# DE-080324.net
KiCad netlist of a schematic drawn in Altium Designer
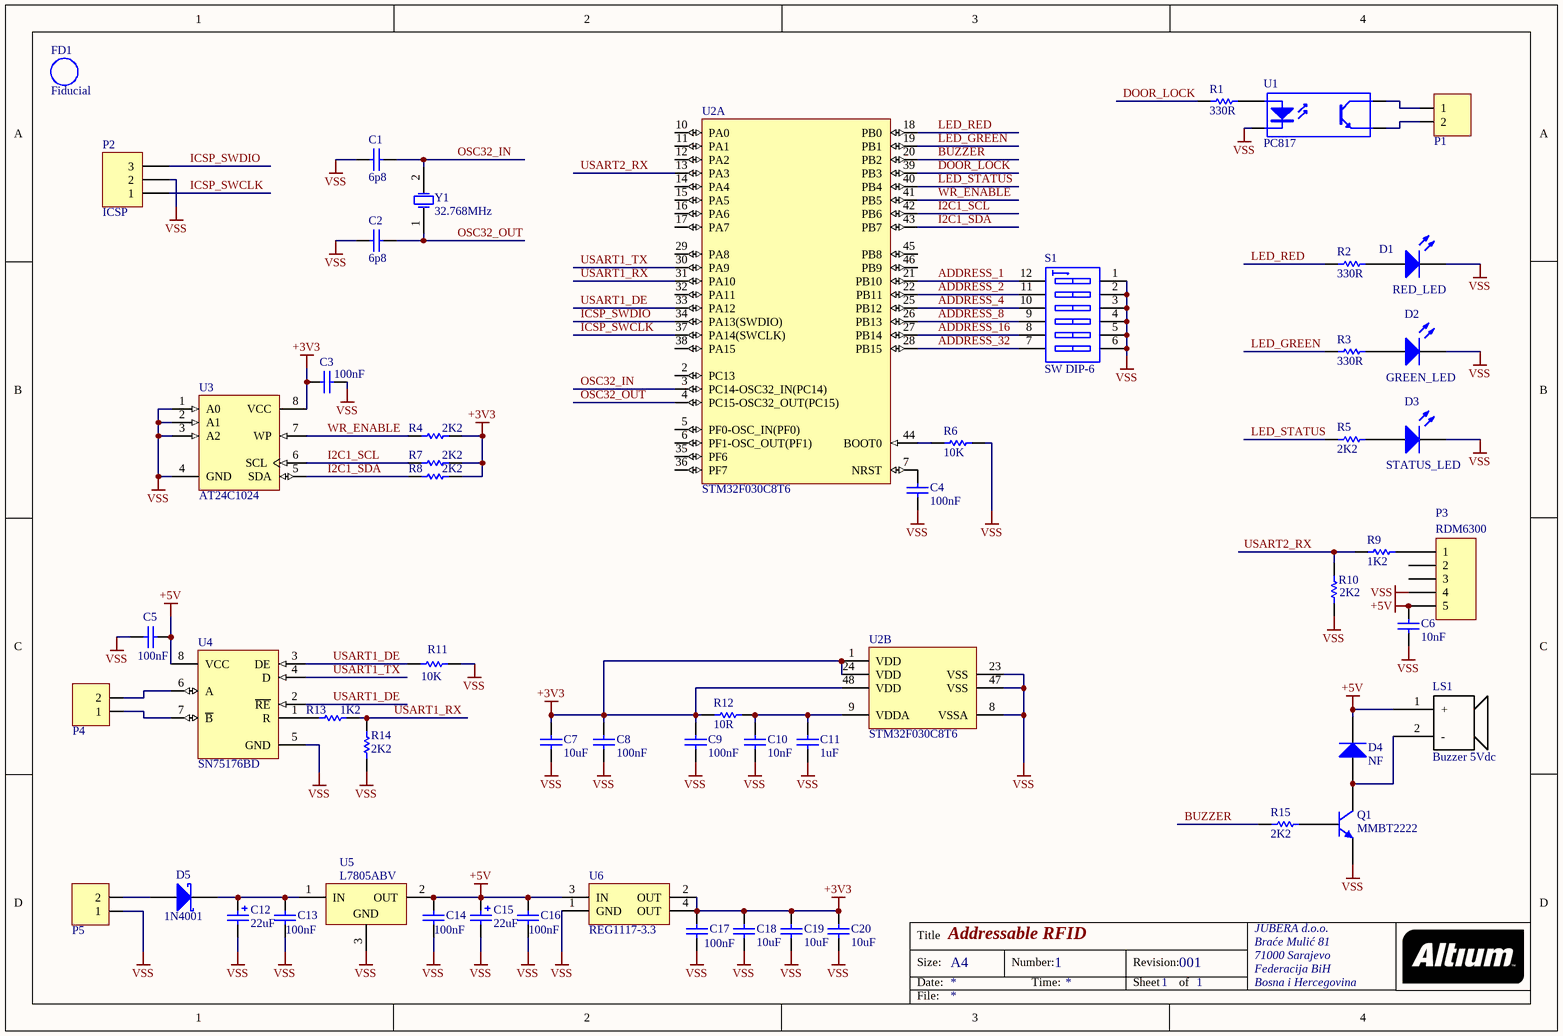
[diagram p0: DE-080324.SchDoc]

(export (version "E")
  (design (tool "Eeschema 10.0.6"))
  (components
    (comp (ref "C1")
      (value "6p8")
      (footprint "0603")
      (description "Ceramic Chip Capacitor - Standard")
      (fields (field (name "PUBLISHER") "Altium Limited"))
      (libsource (lib "DE-080324") (part "C0603"))
    )
    (comp (ref "C2")
      (value "6p8")
      (footprint "0603")
      (description "Ceramic Chip Capacitor - Standard")
      (fields (field (name "PUBLISHER") "Altium Limited"))
      (libsource (lib "DE-080324") (part "C0603"))
    )
    (comp (ref "C3")
      (value "100nF")
      (footprint "0603")
      (description "Ceramic Chip Capacitor - Standard")
      (fields (field (name "PUBLISHER") "Altium Limited"))
      (libsource (lib "DE-080324") (part "C0603"))
    )
    (comp (ref "C4")
      (value "100nF")
      (footprint "0603")
      (description "Ceramic Chip Capacitor - Standard")
      (fields (field (name "PUBLISHER") "Altium Limited"))
      (libsource (lib "DE-080324") (part "C0603"))
    )
    (comp (ref "C5")
      (value "100nF")
      (footprint "0603")
      (description "Ceramic Chip Capacitor - Standard")
      (fields (field (name "PUBLISHER") "Altium Limited"))
      (libsource (lib "DE-080324") (part "C0603"))
    )
    (comp (ref "C6")
      (value "10nF")
      (footprint "0603")
      (description "Ceramic Chip Capacitor - Standard")
      (fields (field (name "PUBLISHER") "Altium Limited"))
      (libsource (lib "DE-080324") (part "C0603"))
    )
    (comp (ref "C7")
      (value "10uF")
      (footprint "0805")
      (description "Ceramic Chip Capacitor - Standard")
      (fields (field (name "PUBLISHER") "Altium Limited"))
      (libsource (lib "DE-080324") (part "C0805"))
    )
    (comp (ref "C8")
      (value "100nF")
      (footprint "0603")
      (description "Ceramic Chip Capacitor - Standard")
      (fields (field (name "PUBLISHER") "Altium Limited"))
      (libsource (lib "DE-080324") (part "C0603"))
    )
    (comp (ref "C9")
      (value "100nF")
      (footprint "0603")
      (description "Ceramic Chip Capacitor - Standard")
      (fields (field (name "PUBLISHER") "Altium Limited"))
      (libsource (lib "DE-080324") (part "C0603"))
    )
    (comp (ref "C10")
      (value "10nF")
      (footprint "0603")
      (description "Ceramic Chip Capacitor - Standard")
      (fields (field (name "PUBLISHER") "Altium Limited"))
      (libsource (lib "DE-080324") (part "C0603"))
    )
    (comp (ref "C11")
      (value "1uF")
      (footprint "0603")
      (description "Ceramic Chip Capacitor - Standard")
      (fields (field (name "PUBLISHER") "Altium Limited"))
      (libsource (lib "DE-080324") (part "C0603"))
    )
    (comp (ref "C12")
      (value "22uF")
      (footprint "CAPPR2-5X11")
      (description "Aluminum Electrolytic Capacitor, Radial Style with Long Leads: 47uF, 35V")
      (fields (field (name "PUBLISHER") "Altium Limited"))
      (libsource (lib "DE-080324") (part "EKA00AA247F00"))
    )
    (comp (ref "C13")
      (value "100nF")
      (footprint "0603")
      (description "Ceramic Chip Capacitor - Standard")
      (fields (field (name "PUBLISHER") "Altium Limited"))
      (libsource (lib "DE-080324") (part "C0603"))
    )
    (comp (ref "C14")
      (value "100nF")
      (footprint "0603")
      (description "Ceramic Chip Capacitor - Standard")
      (fields (field (name "PUBLISHER") "Altium Limited"))
      (libsource (lib "DE-080324") (part "C0603"))
    )
    (comp (ref "C15")
      (value "22uF")
      (footprint "CAPPR2-5X11")
      (description "Aluminum Electrolytic Capacitor, Radial Style with Long Leads: 47uF, 35V")
      (fields (field (name "PUBLISHER") "Altium Limited"))
      (libsource (lib "DE-080324") (part "EKA00AA247F00"))
    )
    (comp (ref "C16")
      (value "100nF")
      (footprint "0603")
      (description "Ceramic Chip Capacitor - Standard")
      (fields (field (name "PUBLISHER") "Altium Limited"))
      (libsource (lib "DE-080324") (part "C0603"))
    )
    (comp (ref "C17")
      (value "100nF")
      (footprint "0603")
      (description "Ceramic Chip Capacitor - Standard")
      (fields (field (name "PUBLISHER") "Altium Limited"))
      (libsource (lib "DE-080324") (part "C0603"))
    )
    (comp (ref "C18")
      (value "10uF")
      (footprint "0805")
      (description "Ceramic Chip Capacitor - Standard")
      (fields (field (name "PUBLISHER") "Altium Limited"))
      (libsource (lib "DE-080324") (part "C0805"))
    )
    (comp (ref "C19")
      (value "10uF")
      (footprint "0805")
      (description "Ceramic Chip Capacitor - Standard")
      (fields (field (name "PUBLISHER") "Altium Limited"))
      (libsource (lib "DE-080324") (part "C0805"))
    )
    (comp (ref "C20")
      (value "10uF")
      (footprint "0805")
      (description "Ceramic Chip Capacitor - Standard")
      (fields (field (name "PUBLISHER") "Altium Limited"))
      (libsource (lib "DE-080324") (part "C0805"))
    )
    (comp (ref "D1")
      (value "RED_LED")
      (footprint "2.0X1.25X1.2")
      (description "Top Mount AS AlInGaP Red Oval Lens High Brightness")
      (fields (field (name "PUBLISHER") "Altium Limited"))
      (libsource (lib "DE-080324") (part "HSMC-C540-F0001"))
    )
    (comp (ref "D2")
      (value "GREEN_LED")
      (footprint "2.0X1.25X1.2")
      (description "Top Mount AS AlInGaP Red Oval Lens High Brightness")
      (fields (field (name "PUBLISHER") "Altium Limited"))
      (libsource (lib "DE-080324") (part "HSMC-C540-F0001"))
    )
    (comp (ref "D3")
      (value "STATUS_LED")
      (footprint "2.0X1.25X1.2")
      (description "Top Mount AS AlInGaP Red Oval Lens High Brightness")
      (fields (field (name "PUBLISHER") "Altium Limited"))
      (libsource (lib "DE-080324") (part "HSMC-C540-F0001"))
    )
    (comp (ref "D4")
      (value "NF")
      (footprint "SOD323")
      (description "General-purpose Diode")
      (fields (field (name "PUBLISHER") "Altium Limited"))
      (libsource (lib "DE-080324") (part "BAS321"))
    )
    (comp (ref "D5")
      (value "1N4001")
      (footprint "SMB")
      (description "Schottky Rectifier")
      (fields (field (name "PUBLISHER") "Altium Limited"))
      (libsource (lib "DE-080324") (part "10BQ100"))
    )
    (comp (ref "FD1")
      (value "Fiducial")
      (footprint "Fiducial")
      (description "Fiduchial mark")
      (libsource (lib "DE-080324") (part "Fiduchial"))
    )
    (comp (ref "LS1")
      (value "Buzzer 5Vdc")
      (footprint "BUZZER")
      (description "5Vdc PCB buzzer")
      (libsource (lib "DE-080324") (part "BUZZER"))
    )
    (comp (ref "P1")
      (value "TERMINAL BLOK 2")
      (footprint "TERMINAL BLOK 2")
      (description "2 pinski terminal blok")
      (libsource (lib "") (part "TERMINAL BLOK 2_1"))
    )
    (comp (ref "P2")
      (value "ICSP")
      (footprint "HDR1X3")
      (description "Header, 3-Pin")
      (fields (field (name "PUBLISHER") "Altium Limited"))
      (libsource (lib "Miscellaneous Connectors") (part "Header 3"))
    )
    (comp (ref "P3")
      (value "RDM6300")
      (footprint "HDR1X5")
      (description "Header, 5-Pin")
      (fields (field (name "PUBLISHER") "Altium Limited"))
      (libsource (lib "Miscellaneous Connectors") (part "Header 5"))
    )
    (comp (ref "P4")
      (value "TERMINAL BLOK 2")
      (footprint "TERMINAL BLOK 2")
      (description "2 pinski terminal blok")
      (libsource (lib "DE-080324") (part "TERMINAL BLOK 2"))
    )
    (comp (ref "P5")
      (value "TERMINAL BLOK 2")
      (footprint "TERMINAL BLOK 2")
      (description "2 pinski terminal blok")
      (libsource (lib "DE-080324") (part "TERMINAL BLOK 2"))
    )
    (comp (ref "Q1")
      (value "MMBT2222")
      (footprint "SOT23_N")
      (description "NPN General-purpose Transistor")
      (fields (field (name "PUBLISHER") "Altium Limited"))
      (libsource (lib "DE-080324") (part "BC817"))
    )
    (comp (ref "R1")
      (value "330R")
      (footprint "ERA-0603")
      (fields (field (name "PUBLISHER") "Altium Limited"))
      (libsource (lib "DE-080324") (part "ERAV"))
    )
    (comp (ref "R2")
      (value "330R")
      (footprint "ERA-0603")
      (fields (field (name "PUBLISHER") "Altium Limited"))
      (libsource (lib "DE-080324") (part "ERAV"))
    )
    (comp (ref "R3")
      (value "330R")
      (footprint "ERA-0603")
      (fields (field (name "PUBLISHER") "Altium Limited"))
      (libsource (lib "DE-080324") (part "ERAV"))
    )
    (comp (ref "R4")
      (value "2K2")
      (footprint "ERA-0603")
      (fields (field (name "PUBLISHER") "Altium Limited"))
      (libsource (lib "DE-080324") (part "ERAV"))
    )
    (comp (ref "R5")
      (value "2K2")
      (footprint "ERA-0603")
      (fields (field (name "PUBLISHER") "Altium Limited"))
      (libsource (lib "DE-080324") (part "ERAV"))
    )
    (comp (ref "R6")
      (value "10K")
      (footprint "ERA-0603")
      (fields (field (name "PUBLISHER") "Altium Limited"))
      (libsource (lib "DE-080324") (part "ERAV"))
    )
    (comp (ref "R7")
      (value "2K2")
      (footprint "ERA-0603")
      (fields (field (name "PUBLISHER") "Altium Limited"))
      (libsource (lib "DE-080324") (part "ERAV"))
    )
    (comp (ref "R8")
      (value "2K2")
      (footprint "ERA-0603")
      (fields (field (name "PUBLISHER") "Altium Limited"))
      (libsource (lib "DE-080324") (part "ERAV"))
    )
    (comp (ref "R9")
      (value "1K2")
      (footprint "ERA-0603")
      (fields (field (name "PUBLISHER") "Altium Limited"))
      (libsource (lib "DE-080324") (part "ERAV"))
    )
    (comp (ref "R10")
      (value "2K2")
      (footprint "ERA-0603")
      (fields (field (name "PUBLISHER") "Altium Limited"))
      (libsource (lib "DE-080324") (part "ERAV"))
    )
    (comp (ref "R11")
      (value "10K")
      (footprint "ERA-0603")
      (fields (field (name "PUBLISHER") "Altium Limited"))
      (libsource (lib "DE-080324") (part "ERAV"))
    )
    (comp (ref "R12")
      (value "10R")
      (footprint "ERA-0603")
      (fields (field (name "PUBLISHER") "Altium Limited"))
      (libsource (lib "DE-080324") (part "ERAV"))
    )
    (comp (ref "R13")
      (value "1K2")
      (footprint "ERA-0603")
      (fields (field (name "PUBLISHER") "Altium Limited"))
      (libsource (lib "DE-080324") (part "ERAV"))
    )
    (comp (ref "R14")
      (value "2K2")
      (footprint "ERA-0603")
      (fields (field (name "PUBLISHER") "Altium Limited"))
      (libsource (lib "DE-080324") (part "ERAV"))
    )
    (comp (ref "R15")
      (value "2K2")
      (footprint "ERA-0603")
      (fields (field (name "PUBLISHER") "Altium Limited"))
      (libsource (lib "DE-080324") (part "ERAV"))
    )
    (comp (ref "S1")
      (value "SW DIP-6")
      (footprint "DIP-12/SW")
      (description "DIP Switch, 6 Position, SPST")
      (fields (field (name "PUBLISHER") "Altium Limited"))
      (libsource (lib "Miscellaneous Devices") (part "SW DIP-6"))
    )
    (comp (ref "U1")
      (value "PC817")
      (footprint "SOP4")
      (description "4-Pin Phototransistor Optocoupler")
      (fields (field (name "PUBLISHER") "Altium Limited"))
      (libsource (lib "DE-080324") (part "PC817 optocoupler"))
    )
    (comp (ref "U2")
      (value "STM32F030C8T6")
      (footprint "STM-LQFP48_N")
      (libsource (lib "STMicroelectronics STM32 F0") (part "STM32F030C8T6"))
    )
    (comp (ref "U3")
      (value "AT24C1024")
      (footprint "8A2_L")
      (fields (field (name "PUBLISHER") "Altium Limited"))
      (libsource (lib "Atmel Memory Serial EEPROM") (part "AT24C02B-TP25-T"))
    )
    (comp (ref "U4")
      (value "SN75176BD")
      (footprint "D008_L")
      (description "Differential Bus Transceiver")
      (fields (field (name "PUBLISHER") "Altium Limited"))
      (libsource (lib "DE-080324") (part "SN75176BD"))
    )
    (comp (ref "U5")
      (value "L7805ABV")
      (footprint "TO220ABN")
      (description "Precision 1A Regulator")
      (fields (field (name "PUBLISHER") "Altium Limited"))
      (libsource (lib "ST Power Mgt Voltage Regulator") (part "L7805ABV"))
    )
    (comp (ref "U6")
      (value "REG1117-3.3")
      (footprint "ZZ311")
      (description "800mA and 1A Low Dropout Positive Regulator 2.85V, 3.3V, 5V, and Adjustable")
      (fields (field (name "PUBLISHER") "Altium Limited"))
      (libsource (lib "DE-080324") (part "REG1117-3.3"))
    )
    (comp (ref "Y1")
      (value "32.768MHz")
      (footprint "R26")
      (description "Tuning Fork Crystal Unit")
      (fields (field (name "PUBLISHER") "Altium Limited"))
      (libsource (lib "DE-080324") (part "R26-32.768"))
    )
  )
  (nets
    (net (code "1") (name "+3V3") (class "Default")
      (node (ref "C17") (pin "2") (pinfunction "2_2") (pintype "passive"))
      (node (ref "C18") (pin "2") (pinfunction "2_2") (pintype "passive"))
      (node (ref "C19") (pin "2") (pinfunction "2_2") (pintype "passive"))
      (node (ref "C20") (pin "2") (pinfunction "2_2") (pintype "passive"))
      (node (ref "C3") (pin "1") (pinfunction "1_1") (pintype "passive"))
      (node (ref "C7") (pin "2") (pinfunction "2_2") (pintype "passive"))
      (node (ref "C8") (pin "2") (pinfunction "2_2") (pintype "passive"))
      (node (ref "C9") (pin "2") (pinfunction "2_2") (pintype "passive"))
      (node (ref "R12") (pin "1") (pinfunction "1_1") (pintype "passive"))
      (node (ref "R4") (pin "2") (pinfunction "2_2") (pintype "passive"))
      (node (ref "R7") (pin "2") (pinfunction "2_2") (pintype "passive"))
      (node (ref "R8") (pin "2") (pinfunction "2_2") (pintype "passive"))
      (node (ref "U2") (pin "1") (pinfunction "VDD_1") (pintype "power_in"))
      (node (ref "U2") (pin "24") (pinfunction "VDD_24") (pintype "power_in"))
      (node (ref "U2") (pin "48") (pinfunction "VDD_48") (pintype "power_in"))
      (node (ref "U3") (pin "8") (pinfunction "VCC_8") (pintype "power_in"))
      (node (ref "U6") (pin "2") (pinfunction "OUT_2") (pintype "power_in"))
      (node (ref "U6") (pin "4") (pinfunction "OUT_4") (pintype "power_in"))
    )
    (net (code "2") (name "+5V") (class "Default")
      (node (ref "C14") (pin "2") (pinfunction "2_2") (pintype "passive"))
      (node (ref "C15") (pin "1") (pinfunction "1_1") (pintype "passive"))
      (node (ref "C16") (pin "2") (pinfunction "2_2") (pintype "passive"))
      (node (ref "C5") (pin "2") (pinfunction "2_2") (pintype "passive"))
      (node (ref "C6") (pin "2") (pinfunction "2_2") (pintype "passive"))
      (node (ref "D4") (pin "1") (pinfunction "K_1") (pintype "passive"))
      (node (ref "LS1") (pin "1") (pinfunction "+_1") (pintype "passive"))
      (node (ref "P3") (pin "5") (pinfunction "5_5") (pintype "passive"))
      (node (ref "U4") (pin "8") (pinfunction "VCC_8") (pintype "power_in"))
      (node (ref "U5") (pin "2") (pinfunction "OUT_2") (pintype "power_in"))
      (node (ref "U6") (pin "3") (pinfunction "IN_3") (pintype "power_in"))
    )
    (net (code "3") (name "/ADDRESS_1") (class "Default")
      (node (ref "S1") (pin "12") (pinfunction "B1_12") (pintype "passive"))
      (node (ref "U2") (pin "21") (pinfunction "PB10_21") (pintype "bidirectional"))
    )
    (net (code "4") (name "/ADDRESS_2") (class "Default")
      (node (ref "S1") (pin "11") (pinfunction "B2_11") (pintype "passive"))
      (node (ref "U2") (pin "22") (pinfunction "PB11_22") (pintype "bidirectional"))
    )
    (net (code "5") (name "/ADDRESS_4") (class "Default")
      (node (ref "S1") (pin "10") (pinfunction "B3_10") (pintype "passive"))
      (node (ref "U2") (pin "25") (pinfunction "PB12_25") (pintype "bidirectional"))
    )
    (net (code "6") (name "/ADDRESS_8") (class "Default")
      (node (ref "S1") (pin "9") (pinfunction "B4_9") (pintype "passive"))
      (node (ref "U2") (pin "26") (pinfunction "PB13_26") (pintype "bidirectional"))
    )
    (net (code "7") (name "/ADDRESS_16") (class "Default")
      (node (ref "S1") (pin "8") (pinfunction "B5_8") (pintype "passive"))
      (node (ref "U2") (pin "27") (pinfunction "PB14_27") (pintype "bidirectional"))
    )
    (net (code "8") (name "/ADDRESS_32") (class "Default")
      (node (ref "S1") (pin "7") (pinfunction "B6_7") (pintype "passive"))
      (node (ref "U2") (pin "28") (pinfunction "PB15_28") (pintype "bidirectional"))
    )
    (net (code "9") (name "/BUZZER") (class "Default")
      (node (ref "R15") (pin "1") (pinfunction "1_1") (pintype "passive"))
      (node (ref "U2") (pin "20") (pinfunction "PB2_20") (pintype "bidirectional"))
    )
    (net (code "10") (name "/DOOR_LOCK") (class "Default")
      (node (ref "R1") (pin "1") (pinfunction "1_1") (pintype "passive"))
      (node (ref "U2") (pin "39") (pinfunction "PB3_39") (pintype "bidirectional"))
    )
    (net (code "11") (name "/I2C1_SCL") (class "Default")
      (node (ref "R7") (pin "1") (pinfunction "1_1") (pintype "passive"))
      (node (ref "U2") (pin "42") (pinfunction "PB6_42") (pintype "bidirectional"))
      (node (ref "U3") (pin "6") (pinfunction "SCL_6") (pintype "input"))
    )
    (net (code "12") (name "/I2C1_SDA") (class "Default")
      (node (ref "R8") (pin "1") (pinfunction "1_1") (pintype "passive"))
      (node (ref "U2") (pin "43") (pinfunction "PB7_43") (pintype "bidirectional"))
      (node (ref "U3") (pin "5") (pinfunction "SDA_5") (pintype "bidirectional"))
    )
    (net (code "13") (name "/ICSP_SWCLK") (class "Default")
      (node (ref "P2") (pin "1") (pinfunction "1_1") (pintype "passive"))
      (node (ref "U2") (pin "37") (pinfunction "PA14(SWCLK)_37") (pintype "bidirectional"))
    )
    (net (code "14") (name "/ICSP_SWDIO") (class "Default")
      (node (ref "P2") (pin "3") (pinfunction "3_3") (pintype "passive"))
      (node (ref "U2") (pin "34") (pinfunction "PA13(SWDIO)_34") (pintype "bidirectional"))
    )
    (net (code "15") (name "/LED_GREEN") (class "Default")
      (node (ref "R3") (pin "1") (pinfunction "1_1") (pintype "passive"))
      (node (ref "U2") (pin "19") (pinfunction "PB1_19") (pintype "bidirectional"))
    )
    (net (code "16") (name "/LED_RED") (class "Default")
      (node (ref "R2") (pin "1") (pinfunction "1_1") (pintype "passive"))
      (node (ref "U2") (pin "18") (pinfunction "PB0_18") (pintype "bidirectional"))
    )
    (net (code "17") (name "/LED_STATUS") (class "Default")
      (node (ref "R5") (pin "1") (pinfunction "1_1") (pintype "passive"))
      (node (ref "U2") (pin "40") (pinfunction "PB4_40") (pintype "bidirectional"))
    )
    (net (code "18") (name "/OSC32_IN") (class "Default")
      (node (ref "C1") (pin "1") (pinfunction "1_1") (pintype "passive"))
      (node (ref "U2") (pin "3") (pinfunction "PC14-OSC32_IN(PC14)_3") (pintype "bidirectional"))
      (node (ref "Y1") (pin "2") (pinfunction "OSC2_2") (pintype "passive"))
    )
    (net (code "19") (name "/OSC32_OUT") (class "Default")
      (node (ref "C2") (pin "1") (pinfunction "1_1") (pintype "passive"))
      (node (ref "U2") (pin "4") (pinfunction "PC15-OSC32_OUT(PC15)_4") (pintype "bidirectional"))
      (node (ref "Y1") (pin "1") (pinfunction "OSC1_1") (pintype "passive"))
    )
    (net (code "20") (name "/USART1_DE") (class "Default")
      (node (ref "R11") (pin "1") (pinfunction "1_1") (pintype "passive"))
      (node (ref "U2") (pin "33") (pinfunction "PA12_33") (pintype "bidirectional"))
      (node (ref "U4") (pin "2") (pinfunction "~{RE}_2") (pintype "input"))
      (node (ref "U4") (pin "3") (pinfunction "DE_3") (pintype "input"))
    )
    (net (code "21") (name "/USART1_RX") (class "Default")
      (node (ref "R13") (pin "2") (pinfunction "2_2") (pintype "passive"))
      (node (ref "R14") (pin "2") (pinfunction "2_2") (pintype "passive"))
      (node (ref "U2") (pin "31") (pinfunction "PA10_31") (pintype "bidirectional"))
    )
    (net (code "22") (name "/USART1_TX") (class "Default")
      (node (ref "U2") (pin "30") (pinfunction "PA9_30") (pintype "bidirectional"))
      (node (ref "U4") (pin "4") (pinfunction "D_4") (pintype "input"))
    )
    (net (code "23") (name "/USART2_RX") (class "Default")
      (node (ref "R10") (pin "2") (pinfunction "2_2") (pintype "passive"))
      (node (ref "R9") (pin "1") (pinfunction "1_1") (pintype "passive"))
      (node (ref "U2") (pin "13") (pinfunction "PA3_13") (pintype "bidirectional"))
    )
    (net (code "24") (name "/WR_ENABLE") (class "Default")
      (node (ref "R4") (pin "1") (pinfunction "1_1") (pintype "passive"))
      (node (ref "U2") (pin "41") (pinfunction "PB5_41") (pintype "bidirectional"))
      (node (ref "U3") (pin "7") (pinfunction "WP_7") (pintype "input"))
    )
    (net (code "25") (name "Net-(D1-A)") (class "Default")
      (node (ref "D1") (pin "1") (pinfunction "A_1") (pintype "passive"))
      (node (ref "R2") (pin "2") (pinfunction "2_2") (pintype "passive"))
    )
    (net (code "26") (name "Net-(D2-A)") (class "Default")
      (node (ref "D2") (pin "1") (pinfunction "A_1") (pintype "passive"))
      (node (ref "R3") (pin "2") (pinfunction "2_2") (pintype "passive"))
    )
    (net (code "27") (name "Net-(D3-A)") (class "Default")
      (node (ref "D3") (pin "1") (pinfunction "A_1") (pintype "passive"))
      (node (ref "R5") (pin "2") (pinfunction "2_2") (pintype "passive"))
    )
    (net (code "28") (name "Net-(D4-A)") (class "Default")
      (node (ref "D4") (pin "2") (pinfunction "A_2") (pintype "passive"))
      (node (ref "LS1") (pin "2") (pinfunction "-_2") (pintype "passive"))
      (node (ref "Q1") (pin "3") (pinfunction "C_3") (pintype "passive"))
    )
    (net (code "29") (name "Net-(D5-A)") (class "Default")
      (node (ref "D5") (pin "1") (pinfunction "A_1") (pintype "passive"))
      (node (ref "P5") (pin "2") (pinfunction "2_2") (pintype "passive"))
    )
    (net (code "30") (name "Net-(D5-K)") (class "Default")
      (node (ref "C12") (pin "1") (pinfunction "1_1") (pintype "passive"))
      (node (ref "C13") (pin "2") (pinfunction "2_2") (pintype "passive"))
      (node (ref "D5") (pin "2") (pinfunction "K_2") (pintype "passive"))
      (node (ref "U5") (pin "1") (pinfunction "IN_1") (pintype "power_in"))
    )
    (net (code "31") (name "Net-(P3-Pad1)") (class "Default")
      (node (ref "P3") (pin "1") (pinfunction "1_1") (pintype "passive"))
      (node (ref "R9") (pin "2") (pinfunction "2_2") (pintype "passive"))
    )
    (net (code "32") (name "Net-(Q1-B)") (class "Default")
      (node (ref "Q1") (pin "1") (pinfunction "B_1") (pintype "passive"))
      (node (ref "R15") (pin "2") (pinfunction "2_2") (pintype "passive"))
    )
    (net (code "33") (name "Net-(U1-A)") (class "Default")
      (node (ref "R1") (pin "2") (pinfunction "2_2") (pintype "passive"))
      (node (ref "U1") (pin "1") (pinfunction "A_1") (pintype "passive"))
    )
    (net (code "34") (name "Net-(U1-C)") (class "Default")
      (node (ref "P1") (pin "1") (pinfunction "1_1") (pintype "passive"))
      (node (ref "U1") (pin "4") (pinfunction "C_4") (pintype "passive"))
    )
    (net (code "35") (name "Net-(U1-E)") (class "Default")
      (node (ref "P1") (pin "2") (pinfunction "2_2") (pintype "passive"))
      (node (ref "U1") (pin "3") (pinfunction "E_3") (pintype "passive"))
    )
    (net (code "36") (name "Net-(U2A-BOOT0)") (class "Default")
      (node (ref "R6") (pin "1") (pinfunction "1_1") (pintype "passive"))
      (node (ref "U2") (pin "44") (pinfunction "BOOT0_44") (pintype "input"))
    )
    (net (code "37") (name "Net-(U2A-NRST)") (class "Default")
      (node (ref "C4") (pin "2") (pinfunction "2_2") (pintype "passive"))
      (node (ref "U2") (pin "7") (pinfunction "NRST_7") (pintype "bidirectional"))
    )
    (net (code "38") (name "Net-(U2B-VDDA)") (class "Default")
      (node (ref "C10") (pin "2") (pinfunction "2_2") (pintype "passive"))
      (node (ref "C11") (pin "2") (pinfunction "2_2") (pintype "passive"))
      (node (ref "R12") (pin "2") (pinfunction "2_2") (pintype "passive"))
      (node (ref "U2") (pin "9") (pinfunction "VDDA_9") (pintype "power_in"))
    )
    (net (code "39") (name "Net-(U4-A)") (class "Default")
      (node (ref "P4") (pin "2") (pinfunction "2_2") (pintype "passive"))
      (node (ref "U4") (pin "6") (pinfunction "A_6") (pintype "bidirectional"))
    )
    (net (code "40") (name "Net-(U4-R)") (class "Default")
      (node (ref "R13") (pin "1") (pinfunction "1_1") (pintype "passive"))
      (node (ref "U4") (pin "1") (pinfunction "R_1") (pintype "tri_state"))
    )
    (net (code "41") (name "Net-(U4-~{B})") (class "Default")
      (node (ref "P4") (pin "1") (pinfunction "1_1") (pintype "passive"))
      (node (ref "U4") (pin "7") (pinfunction "~{B}_7") (pintype "bidirectional"))
    )
    (net (code "42") (name "VSS") (class "Default")
      (node (ref "C1") (pin "2") (pinfunction "2_2") (pintype "passive"))
      (node (ref "C10") (pin "1") (pinfunction "1_1") (pintype "passive"))
      (node (ref "C11") (pin "1") (pinfunction "1_1") (pintype "passive"))
      (node (ref "C12") (pin "2") (pinfunction "2_2") (pintype "passive"))
      (node (ref "C13") (pin "1") (pinfunction "1_1") (pintype "passive"))
      (node (ref "C14") (pin "1") (pinfunction "1_1") (pintype "passive"))
      (node (ref "C15") (pin "2") (pinfunction "2_2") (pintype "passive"))
      (node (ref "C16") (pin "1") (pinfunction "1_1") (pintype "passive"))
      (node (ref "C17") (pin "1") (pinfunction "1_1") (pintype "passive"))
      (node (ref "C18") (pin "1") (pinfunction "1_1") (pintype "passive"))
      (node (ref "C19") (pin "1") (pinfunction "1_1") (pintype "passive"))
      (node (ref "C2") (pin "2") (pinfunction "2_2") (pintype "passive"))
      (node (ref "C20") (pin "1") (pinfunction "1_1") (pintype "passive"))
      (node (ref "C3") (pin "2") (pinfunction "2_2") (pintype "passive"))
      (node (ref "C4") (pin "1") (pinfunction "1_1") (pintype "passive"))
      (node (ref "C5") (pin "1") (pinfunction "1_1") (pintype "passive"))
      (node (ref "C6") (pin "1") (pinfunction "1_1") (pintype "passive"))
      (node (ref "C7") (pin "1") (pinfunction "1_1") (pintype "passive"))
      (node (ref "C8") (pin "1") (pinfunction "1_1") (pintype "passive"))
      (node (ref "C9") (pin "1") (pinfunction "1_1") (pintype "passive"))
      (node (ref "D1") (pin "2") (pinfunction "K_2") (pintype "passive"))
      (node (ref "D2") (pin "2") (pinfunction "K_2") (pintype "passive"))
      (node (ref "D3") (pin "2") (pinfunction "K_2") (pintype "passive"))
      (node (ref "P2") (pin "2") (pinfunction "2_2") (pintype "passive"))
      (node (ref "P3") (pin "4") (pinfunction "4_4") (pintype "passive"))
      (node (ref "P5") (pin "1") (pinfunction "1_1") (pintype "passive"))
      (node (ref "Q1") (pin "2") (pinfunction "E_2") (pintype "passive"))
      (node (ref "R10") (pin "1") (pinfunction "1_1") (pintype "passive"))
      (node (ref "R11") (pin "2") (pinfunction "2_2") (pintype "passive"))
      (node (ref "R14") (pin "1") (pinfunction "1_1") (pintype "passive"))
      (node (ref "R6") (pin "2") (pinfunction "2_2") (pintype "passive"))
      (node (ref "S1") (pin "1") (pinfunction "A1_1") (pintype "passive"))
      (node (ref "S1") (pin "2") (pinfunction "A2_2") (pintype "passive"))
      (node (ref "S1") (pin "3") (pinfunction "A3_3") (pintype "passive"))
      (node (ref "S1") (pin "4") (pinfunction "A4_4") (pintype "passive"))
      (node (ref "S1") (pin "5") (pinfunction "A5_5") (pintype "passive"))
      (node (ref "S1") (pin "6") (pinfunction "A6_6") (pintype "passive"))
      (node (ref "U1") (pin "2") (pinfunction "K_2") (pintype "passive"))
      (node (ref "U2") (pin "23") (pinfunction "VSS_23") (pintype "power_in"))
      (node (ref "U2") (pin "47") (pinfunction "VSS_47") (pintype "power_in"))
      (node (ref "U2") (pin "8") (pinfunction "VSSA_8") (pintype "power_in"))
      (node (ref "U3") (pin "1") (pinfunction "A0_1") (pintype "input"))
      (node (ref "U3") (pin "2") (pinfunction "A1_2") (pintype "input"))
      (node (ref "U3") (pin "3") (pinfunction "A2_3") (pintype "input"))
      (node (ref "U3") (pin "4") (pinfunction "GND_4") (pintype "power_in"))
      (node (ref "U4") (pin "5") (pinfunction "GND_5") (pintype "power_in"))
      (node (ref "U5") (pin "3") (pinfunction "GND_3") (pintype "power_in"))
      (node (ref "U6") (pin "1") (pinfunction "GND_1") (pintype "power_in"))
    )
    (net (code "43") (name "unconnected-(P3-Pad2)") (class "Default")
      (node (ref "P3") (pin "2") (pinfunction "2_2") (pintype "passive"))
    )
    (net (code "44") (name "unconnected-(P3-Pad3)") (class "Default")
      (node (ref "P3") (pin "3") (pinfunction "3_3") (pintype "passive"))
    )
    (net (code "45") (name "unconnected-(U2A-PA0-Pad10)") (class "Default")
      (node (ref "U2") (pin "10") (pinfunction "PA0_10") (pintype "bidirectional"))
    )
    (net (code "46") (name "unconnected-(U2A-PA1-Pad11)") (class "Default")
      (node (ref "U2") (pin "11") (pinfunction "PA1_11") (pintype "bidirectional"))
    )
    (net (code "47") (name "unconnected-(U2A-PA2-Pad12)") (class "Default")
      (node (ref "U2") (pin "12") (pinfunction "PA2_12") (pintype "bidirectional"))
    )
    (net (code "48") (name "unconnected-(U2A-PA4-Pad14)") (class "Default")
      (node (ref "U2") (pin "14") (pinfunction "PA4_14") (pintype "bidirectional"))
    )
    (net (code "49") (name "unconnected-(U2A-PA5-Pad15)") (class "Default")
      (node (ref "U2") (pin "15") (pinfunction "PA5_15") (pintype "bidirectional"))
    )
    (net (code "50") (name "unconnected-(U2A-PA6-Pad16)") (class "Default")
      (node (ref "U2") (pin "16") (pinfunction "PA6_16") (pintype "bidirectional"))
    )
    (net (code "51") (name "unconnected-(U2A-PA7-Pad17)") (class "Default")
      (node (ref "U2") (pin "17") (pinfunction "PA7_17") (pintype "bidirectional"))
    )
    (net (code "52") (name "unconnected-(U2A-PA8-Pad29)") (class "Default")
      (node (ref "U2") (pin "29") (pinfunction "PA8_29") (pintype "bidirectional"))
    )
    (net (code "53") (name "unconnected-(U2A-PA11-Pad32)") (class "Default")
      (node (ref "U2") (pin "32") (pinfunction "PA11_32") (pintype "bidirectional"))
    )
    (net (code "54") (name "unconnected-(U2A-PA15-Pad38)") (class "Default")
      (node (ref "U2") (pin "38") (pinfunction "PA15_38") (pintype "bidirectional"))
    )
    (net (code "55") (name "unconnected-(U2A-PB8-Pad45)") (class "Default")
      (node (ref "U2") (pin "45") (pinfunction "PB8_45") (pintype "bidirectional"))
    )
    (net (code "56") (name "unconnected-(U2A-PB9-Pad46)") (class "Default")
      (node (ref "U2") (pin "46") (pinfunction "PB9_46") (pintype "bidirectional"))
    )
    (net (code "57") (name "unconnected-(U2A-PC13-Pad2)") (class "Default")
      (node (ref "U2") (pin "2") (pinfunction "PC13_2") (pintype "bidirectional"))
    )
    (net (code "58") (name "unconnected-(U2A-PF0-OSC_IN(PF0)-Pad5)") (class "Default")
      (node (ref "U2") (pin "5") (pinfunction "PF0-OSC_IN(PF0)_5") (pintype "bidirectional"))
    )
    (net (code "59") (name "unconnected-(U2A-PF1-OSC_OUT(PF1)-Pad6)") (class "Default")
      (node (ref "U2") (pin "6") (pinfunction "PF1-OSC_OUT(PF1)_6") (pintype "bidirectional"))
    )
    (net (code "60") (name "unconnected-(U2A-PF6-Pad35)") (class "Default")
      (node (ref "U2") (pin "35") (pinfunction "PF6_35") (pintype "bidirectional"))
    )
    (net (code "61") (name "unconnected-(U2A-PF7-Pad36)") (class "Default")
      (node (ref "U2") (pin "36") (pinfunction "PF7_36") (pintype "bidirectional"))
    )
  )
)
